# bombclock_1_0_1.net
KiCad netlist of a schematic drawn in EAGLE
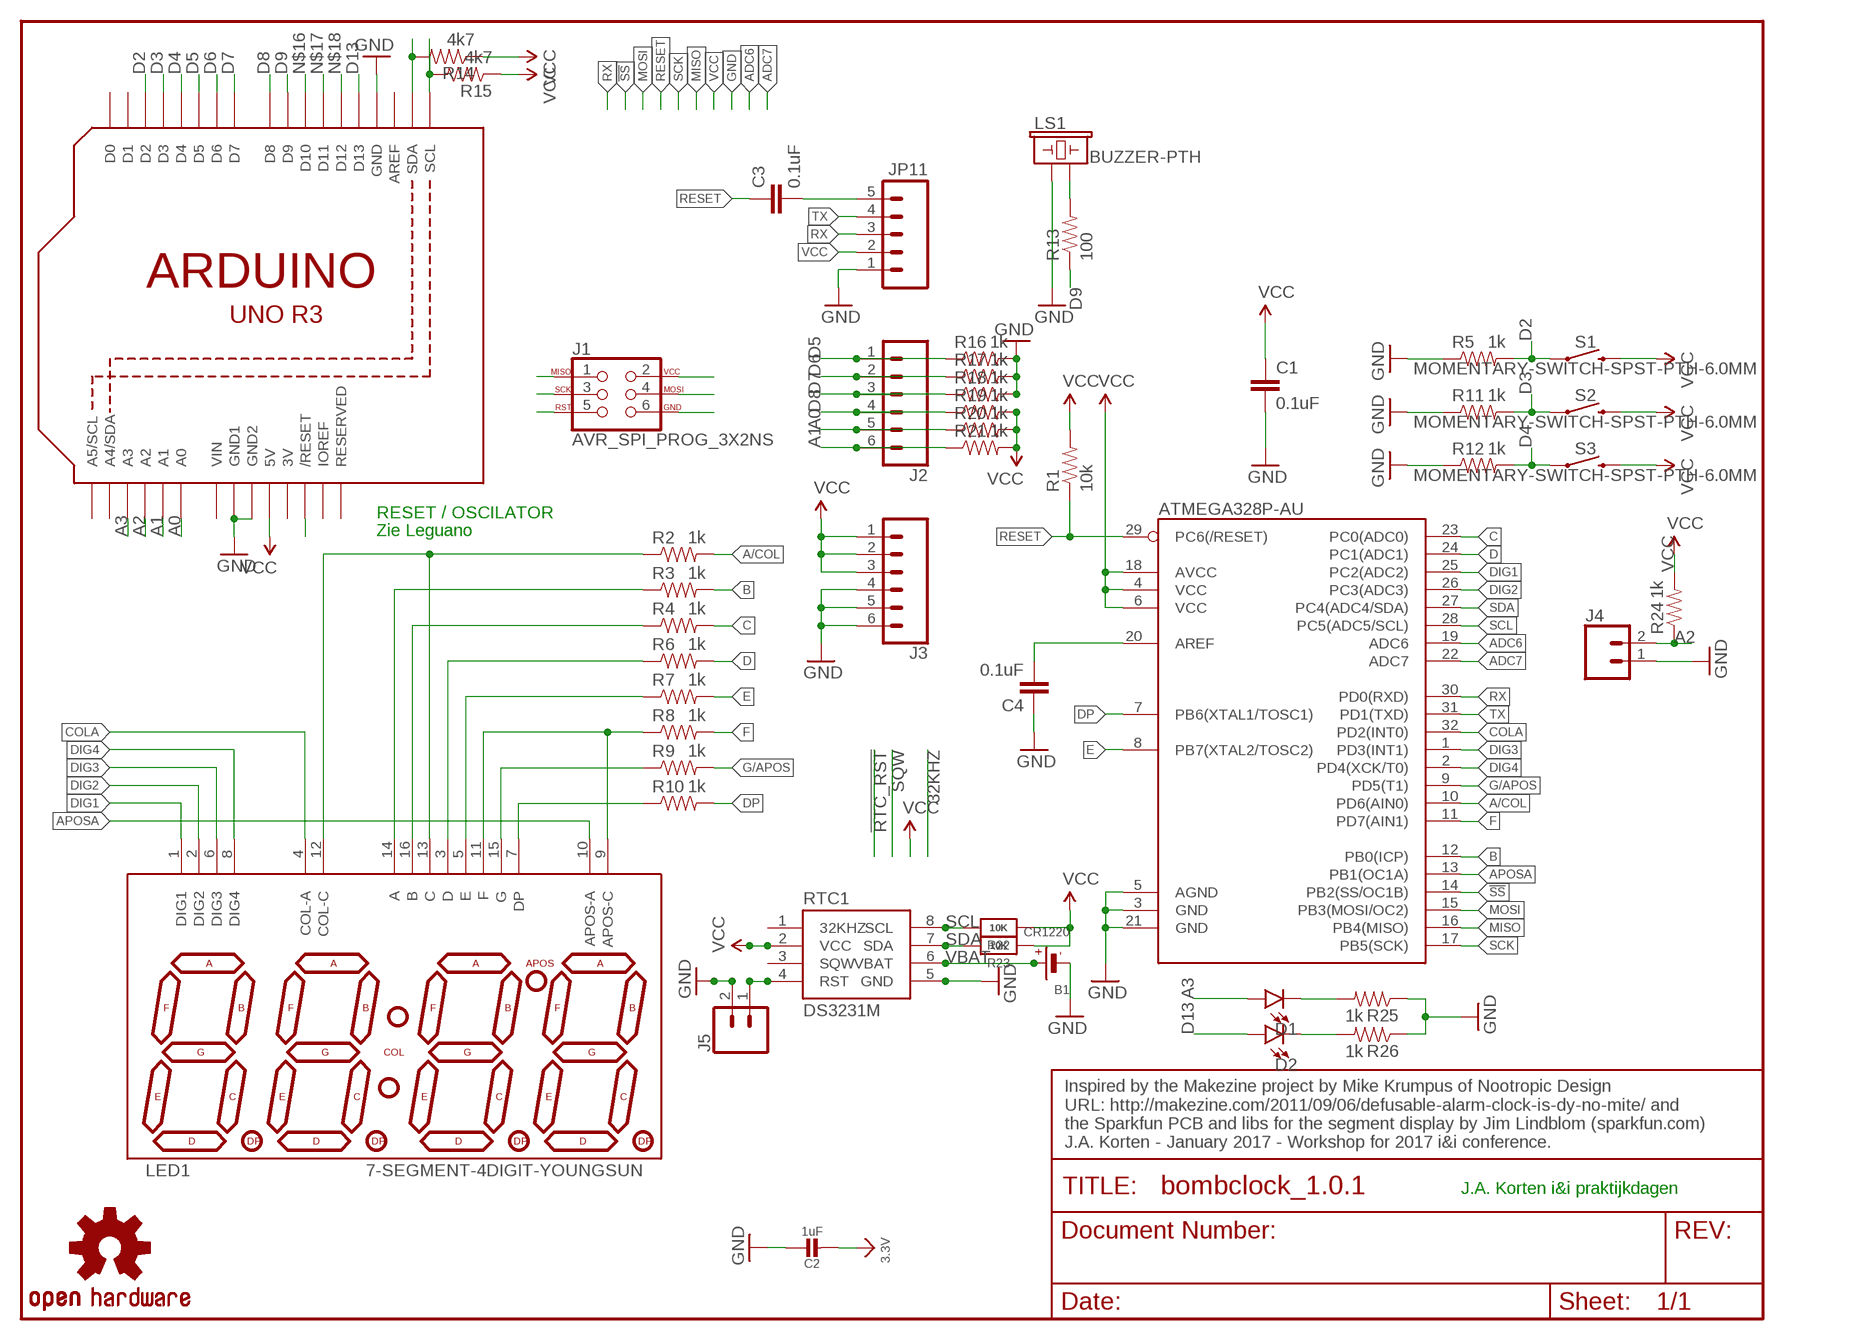
[diagram p0: schematic, sheet 1]

(export (version "E")
  (design (tool "Eeschema 10.0.6"))
  (components
    (comp (ref "ATMEGA328P-AU")
      (value "ATMEGA328P-AU")
      (footprint "eagle-import:TQFP32-08")
      (libsource (lib "eagle-import") (part "ATMEGA168"))
    )
    (comp (ref "B1")
      (value "CR1220")
      (footprint "eagle-import:CR1220")
      (libsource (lib "eagle-import") (part "BATTERYCR1220_SMT"))
    )
    (comp (ref "C1")
      (value "0.1uF")
      (footprint "eagle-import:0402-CAP")
      (libsource (lib "eagle-import") (part "CAP0402-CAP"))
    )
    (comp (ref "C2")
      (value "1uF")
      (footprint "eagle-import:0805-NO")
      (libsource (lib "eagle-import") (part "CAP_CERAMIC0805-NOOUTLINE"))
    )
    (comp (ref "C3")
      (value "0.1uF")
      (footprint "eagle-import:0402-CAP")
      (libsource (lib "eagle-import") (part "SparkFun-Passives_CAP0402-CAP"))
    )
    (comp (ref "C4")
      (value "0.1uF")
      (footprint "eagle-import:0402-CAP")
      (libsource (lib "eagle-import") (part "SparkFun-Passives_CAP0402-CAP"))
    )
    (comp (ref "D1")
      (value "LED5MM")
      (footprint "eagle-import:LED_5MM")
      (libsource (lib "eagle-import") (part "LED5MM"))
    )
    (comp (ref "D2")
      (value "LED5MM")
      (footprint "eagle-import:LED_5MM")
      (libsource (lib "eagle-import") (part "LED5MM"))
    )
    (comp (ref "J1")
      (value "AVR_SPI_PROG_3X2NS")
      (footprint "eagle-import:2X3-NS")
      (libsource (lib "eagle-import") (part "AVR_SPI_PROG_3X2NS"))
    )
    (comp (ref "J2")
      (value "CONN_06SILK_FEMALE_PTH")
      (footprint "eagle-import:1X06")
      (libsource (lib "eagle-import") (part "CONN_06SILK_FEMALE_PTH"))
    )
    (comp (ref "J3")
      (value "CONN_06SILK_FEMALE_PTH")
      (footprint "eagle-import:1X06")
      (libsource (lib "eagle-import") (part "CONN_06SILK_FEMALE_PTH"))
    )
    (comp (ref "J4")
      (value "CONN_02")
      (footprint "eagle-import:1X02")
      (libsource (lib "eagle-import") (part "CONN_02"))
    )
    (comp (ref "J5")
      (value "CONN_02")
      (footprint "eagle-import:1X02")
      (libsource (lib "eagle-import") (part "CONN_02"))
    )
    (comp (ref "JP11")
      (value "M05PTH-NS")
      (footprint "eagle-import:1X05_NO_SILK")
      (libsource (lib "eagle-import") (part "M05PTH-NS"))
    )
    (comp (ref "LED1")
      (value "7-SEGMENT-4DIGIT-YOUNGSUN")
      (footprint "eagle-import:7-SEGMENT-4DIGIT-YOUNGSUN")
      (libsource (lib "eagle-import") (part "7-SEGMENT-4DIGIT-YOUNGSUN"))
    )
    (comp (ref "LS1")
      (value "BUZZER-PTH")
      (footprint "eagle-import:BUZZER-12MM")
      (libsource (lib "eagle-import") (part "BUZZER-PTH"))
    )
    (comp (ref "R1")
      (value "10k")
      (footprint "eagle-import:0402-RES")
      (libsource (lib "eagle-import") (part "RESISTOR0402-RES"))
    )
    (comp (ref "R2")
      (value "1k")
      (footprint "eagle-import:0402-RES")
      (libsource (lib "eagle-import") (part "RESISTOR0402-RES"))
    )
    (comp (ref "R3")
      (value "1k")
      (footprint "eagle-import:0402-RES")
      (libsource (lib "eagle-import") (part "RESISTOR0402-RES"))
    )
    (comp (ref "R4")
      (value "1k")
      (footprint "eagle-import:0402-RES")
      (libsource (lib "eagle-import") (part "RESISTOR0402-RES"))
    )
    (comp (ref "R5")
      (value "1k")
      (footprint "eagle-import:0402-RES")
      (libsource (lib "eagle-import") (part "RESISTOR0402-RES"))
    )
    (comp (ref "R6")
      (value "1k")
      (footprint "eagle-import:0402-RES")
      (libsource (lib "eagle-import") (part "RESISTOR0402-RES"))
    )
    (comp (ref "R7")
      (value "1k")
      (footprint "eagle-import:0402-RES")
      (libsource (lib "eagle-import") (part "RESISTOR0402-RES"))
    )
    (comp (ref "R8")
      (value "1k")
      (footprint "eagle-import:0402-RES")
      (libsource (lib "eagle-import") (part "RESISTOR0402-RES"))
    )
    (comp (ref "R9")
      (value "1k")
      (footprint "eagle-import:0402-RES")
      (libsource (lib "eagle-import") (part "RESISTOR0402-RES"))
    )
    (comp (ref "R10")
      (value "1k")
      (footprint "eagle-import:0402-RES")
      (libsource (lib "eagle-import") (part "RESISTOR0402-RES"))
    )
    (comp (ref "R11")
      (value "1k")
      (footprint "eagle-import:0402-RES")
      (libsource (lib "eagle-import") (part "RESISTOR0402-RES"))
    )
    (comp (ref "R12")
      (value "1k")
      (footprint "eagle-import:0402-RES")
      (libsource (lib "eagle-import") (part "RESISTOR0402-RES"))
    )
    (comp (ref "R13")
      (value "100")
      (footprint "eagle-import:0402-RES")
      (libsource (lib "eagle-import") (part "RESISTOR0402-RES"))
    )
    (comp (ref "R14")
      (value "4k7")
      (footprint "eagle-import:0402-RES")
      (libsource (lib "eagle-import") (part "RESISTOR0402-RES"))
    )
    (comp (ref "R15")
      (value "4k7")
      (footprint "eagle-import:0402-RES")
      (libsource (lib "eagle-import") (part "RESISTOR0402-RES"))
    )
    (comp (ref "R16")
      (value "1k")
      (footprint "eagle-import:0402-RES")
      (libsource (lib "eagle-import") (part "RESISTOR0402-RES"))
    )
    (comp (ref "R17")
      (value "1k")
      (footprint "eagle-import:0402-RES")
      (libsource (lib "eagle-import") (part "RESISTOR0402-RES"))
    )
    (comp (ref "R18")
      (value "1k")
      (footprint "eagle-import:0402-RES")
      (libsource (lib "eagle-import") (part "RESISTOR0402-RES"))
    )
    (comp (ref "R19")
      (value "1k")
      (footprint "eagle-import:0402-RES")
      (libsource (lib "eagle-import") (part "RESISTOR0402-RES"))
    )
    (comp (ref "R20")
      (value "1k")
      (footprint "eagle-import:0402-RES")
      (libsource (lib "eagle-import") (part "RESISTOR0402-RES"))
    )
    (comp (ref "R21")
      (value "1k")
      (footprint "eagle-import:0402-RES")
      (libsource (lib "eagle-import") (part "RESISTOR0402-RES"))
    )
    (comp (ref "R22")
      (value "10K")
      (footprint "eagle-import:0805-NO")
      (libsource (lib "eagle-import") (part "RESISTOR0805_NOOUTLINE"))
    )
    (comp (ref "R23")
      (value "10K")
      (footprint "eagle-import:0805-NO")
      (libsource (lib "eagle-import") (part "RESISTOR0805_NOOUTLINE"))
    )
    (comp (ref "R24")
      (value "1k")
      (footprint "eagle-import:0402-RES")
      (libsource (lib "eagle-import") (part "RESISTOR0402-RES"))
    )
    (comp (ref "R25")
      (value "1k")
      (footprint "eagle-import:0402-RES")
      (libsource (lib "eagle-import") (part "RESISTOR0402-RES"))
    )
    (comp (ref "R26")
      (value "1k")
      (footprint "eagle-import:0402-RES")
      (libsource (lib "eagle-import") (part "RESISTOR0402-RES"))
    )
    (comp (ref "RTC1")
      (value "DS3231M")
      (footprint "eagle-import:SO08")
      (libsource (lib "eagle-import") (part "DS3231M"))
    )
    (comp (ref "S1")
      (value "MOMENTARY-SWITCH-SPST-PTH-6.0MM")
      (footprint "eagle-import:TACTILE_SWITCH_PTH_6.0MM")
      (libsource (lib "eagle-import") (part "MOMENTARY-SWITCH-SPST-PTH-6.0MM"))
    )
    (comp (ref "S2")
      (value "MOMENTARY-SWITCH-SPST-PTH-6.0MM")
      (footprint "eagle-import:TACTILE_SWITCH_PTH_6.0MM")
      (libsource (lib "eagle-import") (part "MOMENTARY-SWITCH-SPST-PTH-6.0MM"))
    )
    (comp (ref "S3")
      (value "MOMENTARY-SWITCH-SPST-PTH-6.0MM")
      (footprint "eagle-import:TACTILE_SWITCH_PTH_6.0MM")
      (libsource (lib "eagle-import") (part "MOMENTARY-SWITCH-SPST-PTH-6.0MM"))
    )
    (comp (ref "U$4")
      (value "OSHW-LOGOS")
      (footprint "eagle-import:OSHW-LOGO-S")
      (libsource (lib "eagle-import") (part "OSHW-LOGOS"))
    )
    (comp (ref "U1")
      (value "ARDUINOR3-DIMENSION")
      (footprint "eagle-import:ARDUINOR3")
      (libsource (lib "eagle-import") (part "ARDUINOR3-DIMENSION"))
    )
  )
  (nets
    (net (code "1") (name "/3V") (class "Default")
      (node (ref "U1") (pin "3V") (pinfunction "3V_3V") (pintype "power_in"))
    )
    (net (code "3") (name "/A0") (class "Default")
      (node (ref "J2") (pin "5") (pinfunction "5_5") (pintype "passive"))
      (node (ref "R20") (pin "1") (pinfunction "1_1") (pintype "passive"))
      (node (ref "U1") (pin "A0") (pinfunction "A0_A0") (pintype "bidirectional"))
    )
    (net (code "4") (name "/A1") (class "Default")
      (node (ref "J2") (pin "6") (pinfunction "6_6") (pintype "passive"))
      (node (ref "R21") (pin "1") (pinfunction "1_1") (pintype "passive"))
      (node (ref "U1") (pin "A1") (pinfunction "A1_A1") (pintype "bidirectional"))
    )
    (net (code "5") (name "/A2") (class "Default")
      (node (ref "J4") (pin "2") (pinfunction "2_2") (pintype "passive"))
      (node (ref "R24") (pin "1") (pinfunction "1_1") (pintype "passive"))
      (node (ref "U1") (pin "A2") (pinfunction "A2_A2") (pintype "bidirectional"))
    )
    (net (code "6") (name "/A3") (class "Default")
      (node (ref "D1") (pin "A") (pinfunction "A_A") (pintype "passive"))
      (node (ref "U1") (pin "A3") (pinfunction "A3_A3") (pintype "bidirectional"))
    )
    (net (code "7") (name "/D2") (class "Default")
      (node (ref "R5") (pin "2") (pinfunction "2_2") (pintype "passive"))
      (node (ref "S1") (pin "1") (pinfunction "1_1") (pintype "passive"))
      (node (ref "U1") (pin "D2") (pinfunction "D2_D2") (pintype "bidirectional"))
    )
    (net (code "8") (name "/D3") (class "Default")
      (node (ref "R11") (pin "2") (pinfunction "2_2") (pintype "passive"))
      (node (ref "S2") (pin "1") (pinfunction "1_1") (pintype "passive"))
      (node (ref "U1") (pin "D3") (pinfunction "D3_D3") (pintype "bidirectional"))
    )
    (net (code "9") (name "/D4") (class "Default")
      (node (ref "R12") (pin "2") (pinfunction "2_2") (pintype "passive"))
      (node (ref "S3") (pin "1") (pinfunction "1_1") (pintype "passive"))
      (node (ref "U1") (pin "D4") (pinfunction "D4_D4") (pintype "bidirectional"))
    )
    (net (code "10") (name "/D5") (class "Default")
      (node (ref "J2") (pin "1") (pinfunction "1_1") (pintype "passive"))
      (node (ref "R16") (pin "1") (pinfunction "1_1") (pintype "passive"))
      (node (ref "U1") (pin "D5") (pinfunction "D5_D5") (pintype "bidirectional"))
    )
    (net (code "11") (name "/D6") (class "Default")
      (node (ref "J2") (pin "2") (pinfunction "2_2") (pintype "passive"))
      (node (ref "R17") (pin "1") (pinfunction "1_1") (pintype "passive"))
      (node (ref "U1") (pin "D6") (pinfunction "D6_D6") (pintype "bidirectional"))
    )
    (net (code "12") (name "/D7") (class "Default")
      (node (ref "J2") (pin "3") (pinfunction "3_3") (pintype "passive"))
      (node (ref "R18") (pin "1") (pinfunction "1_1") (pintype "passive"))
      (node (ref "U1") (pin "D7") (pinfunction "D7_D7") (pintype "bidirectional"))
    )
    (net (code "13") (name "/D8") (class "Default")
      (node (ref "J2") (pin "4") (pinfunction "4_4") (pintype "passive"))
      (node (ref "R19") (pin "1") (pinfunction "1_1") (pintype "passive"))
      (node (ref "U1") (pin "D8") (pinfunction "D8_D8") (pintype "bidirectional"))
    )
    (net (code "14") (name "/D9") (class "Default")
      (node (ref "R13") (pin "1") (pinfunction "1_1") (pintype "passive"))
      (node (ref "U1") (pin "D9") (pinfunction "D9_D9") (pintype "bidirectional"))
    )
    (net (code "15") (name "/D13") (class "Default")
      (node (ref "D2") (pin "A") (pinfunction "A_A") (pintype "passive"))
      (node (ref "U1") (pin "D13") (pinfunction "D13_D13") (pintype "bidirectional"))
    )
    (net (code "16") (name "/N$16") (class "Default")
      (node (ref "U1") (pin "D10") (pinfunction "D10_D10") (pintype "bidirectional"))
    )
    (net (code "17") (name "/N$17") (class "Default")
      (node (ref "U1") (pin "D11") (pinfunction "D11_D11") (pintype "bidirectional"))
    )
    (net (code "18") (name "/N$18") (class "Default")
      (node (ref "U1") (pin "D12") (pinfunction "D12_D12") (pintype "bidirectional"))
    )
    (net (code "20") (name "/VBAT") (class "Default")
      (node (ref "B1") (pin "+$1") (pinfunction "+_+$1") (pintype "passive"))
      (node (ref "RTC1") (pin "6") (pinfunction "VBAT_6") (pintype "power_in"))
    )
    (net (code "21") (name "/VIN") (class "Default")
      (node (ref "U1") (pin "VIN") (pinfunction "VIN_VIN") (pintype "power_in"))
    )
    (net (code "23") (name "/~{SS}") (class "Default")
      (node (ref "ATMEGA328P-AU") (pin "14") (pinfunction "PB2(SS/OC1B)_14") (pintype "bidirectional"))
    )
    (net (code "24") (name "3.3V") (class "Default")
      (node (ref "C2") (pin "2") (pinfunction "2_2") (pintype "passive"))
    )
    (net (code "25") (name "ADC6") (class "Default")
      (node (ref "ATMEGA328P-AU") (pin "19") (pinfunction "ADC6_19") (pintype "bidirectional"))
    )
    (net (code "26") (name "ADC7") (class "Default")
      (node (ref "ATMEGA328P-AU") (pin "22") (pinfunction "ADC7_22") (pintype "bidirectional"))
    )
    (net (code "27") (name "APOSA") (class "Default")
      (node (ref "ATMEGA328P-AU") (pin "13") (pinfunction "PB1(OC1A)_13") (pintype "bidirectional"))
      (node (ref "LED1") (pin "10") (pinfunction "APOS-A_10") (pintype "bidirectional"))
    )
    (net (code "28") (name "A{slash}COL") (class "Default")
      (node (ref "ATMEGA328P-AU") (pin "10") (pinfunction "PD6(AIN0)_10") (pintype "bidirectional"))
      (node (ref "R2") (pin "2") (pinfunction "2_2") (pintype "passive"))
    )
    (net (code "29") (name "B") (class "Default")
      (node (ref "ATMEGA328P-AU") (pin "12") (pinfunction "PB0(ICP)_12") (pintype "bidirectional"))
      (node (ref "R3") (pin "2") (pinfunction "2_2") (pintype "passive"))
    )
    (net (code "30") (name "C") (class "Default")
      (node (ref "ATMEGA328P-AU") (pin "23") (pinfunction "PC0(ADC0)_23") (pintype "bidirectional"))
      (node (ref "R4") (pin "2") (pinfunction "2_2") (pintype "passive"))
    )
    (net (code "31") (name "COLA") (class "Default")
      (node (ref "ATMEGA328P-AU") (pin "32") (pinfunction "PD2(INT0)_32") (pintype "bidirectional"))
      (node (ref "LED1") (pin "4") (pinfunction "COL-A_4") (pintype "bidirectional"))
    )
    (net (code "32") (name "D") (class "Default")
      (node (ref "ATMEGA328P-AU") (pin "24") (pinfunction "PC1(ADC1)_24") (pintype "bidirectional"))
      (node (ref "R6") (pin "2") (pinfunction "2_2") (pintype "passive"))
    )
    (net (code "33") (name "DIG1") (class "Default")
      (node (ref "ATMEGA328P-AU") (pin "25") (pinfunction "PC2(ADC2)_25") (pintype "bidirectional"))
      (node (ref "LED1") (pin "1") (pinfunction "DIG1_1") (pintype "bidirectional"))
    )
    (net (code "34") (name "DIG2") (class "Default")
      (node (ref "ATMEGA328P-AU") (pin "26") (pinfunction "PC3(ADC3)_26") (pintype "bidirectional"))
      (node (ref "LED1") (pin "2") (pinfunction "DIG2_2") (pintype "bidirectional"))
    )
    (net (code "35") (name "DIG3") (class "Default")
      (node (ref "ATMEGA328P-AU") (pin "1") (pinfunction "PD3(INT1)_1") (pintype "bidirectional"))
      (node (ref "LED1") (pin "6") (pinfunction "DIG3_6") (pintype "bidirectional"))
    )
    (net (code "36") (name "DIG4") (class "Default")
      (node (ref "ATMEGA328P-AU") (pin "2") (pinfunction "PD4(XCK/T0)_2") (pintype "bidirectional"))
      (node (ref "LED1") (pin "8") (pinfunction "DIG4_8") (pintype "bidirectional"))
    )
    (net (code "37") (name "DP") (class "Default")
      (node (ref "ATMEGA328P-AU") (pin "7") (pinfunction "PB6(XTAL1/TOSC1)_7") (pintype "bidirectional"))
      (node (ref "R10") (pin "2") (pinfunction "2_2") (pintype "passive"))
    )
    (net (code "38") (name "E") (class "Default")
      (node (ref "ATMEGA328P-AU") (pin "8") (pinfunction "PB7(XTAL2/TOSC2)_8") (pintype "bidirectional"))
      (node (ref "R7") (pin "2") (pinfunction "2_2") (pintype "passive"))
    )
    (net (code "39") (name "F") (class "Default")
      (node (ref "ATMEGA328P-AU") (pin "11") (pinfunction "PD7(AIN1)_11") (pintype "bidirectional"))
      (node (ref "R8") (pin "2") (pinfunction "2_2") (pintype "passive"))
    )
    (net (code "40") (name "GND") (class "Default")
      (node (ref "ATMEGA328P-AU") (pin "21") (pinfunction "GND_21") (pintype "bidirectional"))
      (node (ref "ATMEGA328P-AU") (pin "3") (pinfunction "GND_3") (pintype "bidirectional"))
      (node (ref "ATMEGA328P-AU") (pin "5") (pinfunction "AGND_5") (pintype "bidirectional"))
      (node (ref "B1") (pin "-") (pinfunction "-_-") (pintype "passive"))
      (node (ref "C1") (pin "2") (pinfunction "2_2") (pintype "passive"))
      (node (ref "C2") (pin "1") (pinfunction "1_1") (pintype "passive"))
      (node (ref "C4") (pin "1") (pinfunction "1_1") (pintype "passive"))
      (node (ref "J1") (pin "6") (pinfunction "6_6") (pintype "passive"))
      (node (ref "J3") (pin "4") (pinfunction "4_4") (pintype "passive"))
      (node (ref "J3") (pin "5") (pinfunction "5_5") (pintype "passive"))
      (node (ref "J3") (pin "6") (pinfunction "6_6") (pintype "passive"))
      (node (ref "J4") (pin "1") (pinfunction "1_1") (pintype "passive"))
      (node (ref "J5") (pin "2") (pinfunction "2_2") (pintype "passive"))
      (node (ref "JP11") (pin "1") (pinfunction "1_1") (pintype "passive"))
      (node (ref "LS1") (pin "+") (pinfunction "1_+") (pintype "passive"))
      (node (ref "R11") (pin "1") (pinfunction "1_1") (pintype "passive"))
      (node (ref "R12") (pin "1") (pinfunction "1_1") (pintype "passive"))
      (node (ref "R16") (pin "2") (pinfunction "2_2") (pintype "passive"))
      (node (ref "R17") (pin "2") (pinfunction "2_2") (pintype "passive"))
      (node (ref "R18") (pin "2") (pinfunction "2_2") (pintype "passive"))
      (node (ref "R25") (pin "1") (pinfunction "1_1") (pintype "passive"))
      (node (ref "R26") (pin "1") (pinfunction "1_1") (pintype "passive"))
      (node (ref "R5") (pin "1") (pinfunction "1_1") (pintype "passive"))
      (node (ref "RTC1") (pin "5") (pinfunction "GND_5") (pintype "power_in"))
      (node (ref "U1") (pin "GND") (pinfunction "GND_GND") (pintype "power_in"))
      (node (ref "U1") (pin "GND1") (pinfunction "GND1_GND1") (pintype "power_in"))
      (node (ref "U1") (pin "GND2") (pinfunction "GND2_GND2") (pintype "power_in"))
    )
    (net (code "41") (name "G{slash}APOS") (class "Default")
      (node (ref "ATMEGA328P-AU") (pin "9") (pinfunction "PD5(T1)_9") (pintype "bidirectional"))
      (node (ref "R9") (pin "2") (pinfunction "2_2") (pintype "passive"))
    )
    (net (code "42") (name "MISO") (class "Default")
      (node (ref "ATMEGA328P-AU") (pin "16") (pinfunction "PB4(MISO)_16") (pintype "bidirectional"))
      (node (ref "J1") (pin "1") (pinfunction "1_1") (pintype "passive"))
    )
    (net (code "43") (name "MOSI") (class "Default")
      (node (ref "ATMEGA328P-AU") (pin "15") (pinfunction "PB3(MOSI/OC2)_15") (pintype "bidirectional"))
      (node (ref "J1") (pin "4") (pinfunction "4_4") (pintype "passive"))
    )
    (net (code "44") (name "Net-(ATMEGA328P-AU-AREF)") (class "Default")
      (node (ref "ATMEGA328P-AU") (pin "20") (pinfunction "AREF_20") (pintype "bidirectional"))
      (node (ref "C4") (pin "2") (pinfunction "2_2") (pintype "passive"))
    )
    (net (code "45") (name "Net-(C3-Pad2)") (class "Default")
      (node (ref "C3") (pin "2") (pinfunction "2_2") (pintype "passive"))
      (node (ref "JP11") (pin "5") (pinfunction "5_5") (pintype "passive"))
    )
    (net (code "46") (name "Net-(D1-C)") (class "Default")
      (node (ref "D1") (pin "K") (pinfunction "C_K") (pintype "passive"))
      (node (ref "R25") (pin "2") (pinfunction "2_2") (pintype "passive"))
    )
    (net (code "47") (name "Net-(D2-C)") (class "Default")
      (node (ref "D2") (pin "K") (pinfunction "C_K") (pintype "passive"))
      (node (ref "R26") (pin "2") (pinfunction "2_2") (pintype "passive"))
    )
    (net (code "48") (name "Net-(LED1-A)") (class "Default")
      (node (ref "LED1") (pin "14") (pinfunction "A_14") (pintype "bidirectional"))
      (node (ref "R3") (pin "1") (pinfunction "1_1") (pintype "passive"))
    )
    (net (code "49") (name "Net-(LED1-APOS-C)") (class "Default")
      (node (ref "LED1") (pin "11") (pinfunction "F_11") (pintype "bidirectional"))
      (node (ref "LED1") (pin "9") (pinfunction "APOS-C_9") (pintype "bidirectional"))
      (node (ref "R8") (pin "1") (pinfunction "1_1") (pintype "passive"))
    )
    (net (code "50") (name "Net-(LED1-B)") (class "Default")
      (node (ref "LED1") (pin "16") (pinfunction "B_16") (pintype "bidirectional"))
      (node (ref "R4") (pin "1") (pinfunction "1_1") (pintype "passive"))
    )
    (net (code "51") (name "Net-(LED1-C)") (class "Default")
      (node (ref "LED1") (pin "12") (pinfunction "COL-C_12") (pintype "bidirectional"))
      (node (ref "LED1") (pin "13") (pinfunction "C_13") (pintype "bidirectional"))
      (node (ref "R2") (pin "1") (pinfunction "1_1") (pintype "passive"))
    )
    (net (code "52") (name "Net-(LED1-D)") (class "Default")
      (node (ref "LED1") (pin "3") (pinfunction "D_3") (pintype "bidirectional"))
      (node (ref "R6") (pin "1") (pinfunction "1_1") (pintype "passive"))
    )
    (net (code "53") (name "Net-(LED1-DP)") (class "Default")
      (node (ref "LED1") (pin "7") (pinfunction "DP_7") (pintype "bidirectional"))
      (node (ref "R10") (pin "1") (pinfunction "1_1") (pintype "passive"))
    )
    (net (code "54") (name "Net-(LED1-E)") (class "Default")
      (node (ref "LED1") (pin "5") (pinfunction "E_5") (pintype "bidirectional"))
      (node (ref "R7") (pin "1") (pinfunction "1_1") (pintype "passive"))
    )
    (net (code "55") (name "Net-(LED1-G)") (class "Default")
      (node (ref "LED1") (pin "15") (pinfunction "G_15") (pintype "bidirectional"))
      (node (ref "R9") (pin "1") (pinfunction "1_1") (pintype "passive"))
    )
    (net (code "56") (name "Net-(LS1-2)") (class "Default")
      (node (ref "LS1") (pin "-") (pinfunction "2_-") (pintype "passive"))
      (node (ref "R13") (pin "2") (pinfunction "2_2") (pintype "passive"))
    )
    (net (code "57") (name "Net-(RTC1-RST)") (class "Default")
      (node (ref "J5") (pin "1") (pinfunction "1_1") (pintype "passive"))
      (node (ref "RTC1") (pin "4") (pinfunction "RST_4") (pintype "bidirectional"))
    )
    (net (code "58") (name "RESET") (class "Default")
      (node (ref "ATMEGA328P-AU") (pin "29") (pinfunction "PC6(/RESET)_29") (pintype "bidirectional"))
      (node (ref "C3") (pin "1") (pinfunction "1_1") (pintype "passive"))
      (node (ref "J1") (pin "5") (pinfunction "5_5") (pintype "passive"))
      (node (ref "R1") (pin "1") (pinfunction "1_1") (pintype "passive"))
    )
    (net (code "59") (name "RX") (class "Default")
      (node (ref "ATMEGA328P-AU") (pin "30") (pinfunction "PD0(RXD)_30") (pintype "bidirectional"))
      (node (ref "JP11") (pin "3") (pinfunction "3_3") (pintype "passive"))
    )
    (net (code "60") (name "SCK") (class "Default")
      (node (ref "ATMEGA328P-AU") (pin "17") (pinfunction "PB5(SCK)_17") (pintype "bidirectional"))
      (node (ref "J1") (pin "3") (pinfunction "3_3") (pintype "passive"))
    )
    (net (code "61") (name "SCL") (class "Default")
      (node (ref "ATMEGA328P-AU") (pin "28") (pinfunction "PC5(ADC5/SCL)_28") (pintype "bidirectional"))
      (node (ref "R15") (pin "2") (pinfunction "2_2") (pintype "passive"))
      (node (ref "R22") (pin "2") (pinfunction "2_2") (pintype "passive"))
      (node (ref "RTC1") (pin "8") (pinfunction "SCL_8") (pintype "bidirectional"))
      (node (ref "U1") (pin "SCL") (pinfunction "SCL_SCL") (pintype "bidirectional"))
    )
    (net (code "62") (name "SDA") (class "Default")
      (node (ref "ATMEGA328P-AU") (pin "27") (pinfunction "PC4(ADC4/SDA)_27") (pintype "bidirectional"))
      (node (ref "R14") (pin "2") (pinfunction "2_2") (pintype "passive"))
      (node (ref "R23") (pin "2") (pinfunction "2_2") (pintype "passive"))
      (node (ref "RTC1") (pin "7") (pinfunction "SDA_7") (pintype "bidirectional"))
      (node (ref "U1") (pin "SDA") (pinfunction "SDA_SDA") (pintype "bidirectional"))
    )
    (net (code "63") (name "TX") (class "Default")
      (node (ref "ATMEGA328P-AU") (pin "31") (pinfunction "PD1(TXD)_31") (pintype "bidirectional"))
      (node (ref "JP11") (pin "4") (pinfunction "4_4") (pintype "passive"))
    )
    (net (code "64") (name "VCC") (class "Default")
      (node (ref "ATMEGA328P-AU") (pin "18") (pinfunction "AVCC_18") (pintype "bidirectional"))
      (node (ref "ATMEGA328P-AU") (pin "4") (pinfunction "VCC_4") (pintype "bidirectional"))
      (node (ref "ATMEGA328P-AU") (pin "6") (pinfunction "VCC_6") (pintype "bidirectional"))
      (node (ref "C1") (pin "1") (pinfunction "1_1") (pintype "passive"))
      (node (ref "J1") (pin "2") (pinfunction "2_2") (pintype "passive"))
      (node (ref "J3") (pin "1") (pinfunction "1_1") (pintype "passive"))
      (node (ref "J3") (pin "2") (pinfunction "2_2") (pintype "passive"))
      (node (ref "J3") (pin "3") (pinfunction "3_3") (pintype "passive"))
      (node (ref "JP11") (pin "2") (pinfunction "2_2") (pintype "passive"))
      (node (ref "R1") (pin "2") (pinfunction "2_2") (pintype "passive"))
      (node (ref "R14") (pin "1") (pinfunction "1_1") (pintype "passive"))
      (node (ref "R15") (pin "1") (pinfunction "1_1") (pintype "passive"))
      (node (ref "R19") (pin "2") (pinfunction "2_2") (pintype "passive"))
      (node (ref "R20") (pin "2") (pinfunction "2_2") (pintype "passive"))
      (node (ref "R21") (pin "2") (pinfunction "2_2") (pintype "passive"))
      (node (ref "R22") (pin "1") (pinfunction "1_1") (pintype "passive"))
      (node (ref "R23") (pin "1") (pinfunction "1_1") (pintype "passive"))
      (node (ref "R24") (pin "2") (pinfunction "2_2") (pintype "passive"))
      (node (ref "RTC1") (pin "2") (pinfunction "VCC_2") (pintype "power_in"))
      (node (ref "S1") (pin "3") (pinfunction "2_3") (pintype "passive"))
      (node (ref "S2") (pin "3") (pinfunction "2_3") (pintype "passive"))
      (node (ref "S3") (pin "3") (pinfunction "2_3") (pintype "passive"))
      (node (ref "U1") (pin "5V") (pinfunction "5V_5V") (pintype "power_in"))
    )
    (net (code "65") (name "unconnected-(RTC1-32KHZ-Pad1)") (class "Default")
      (node (ref "RTC1") (pin "1") (pinfunction "32KHZ_1") (pintype "output"))
    )
    (net (code "66") (name "unconnected-(RTC1-SQW-Pad3)") (class "Default")
      (node (ref "RTC1") (pin "3") (pinfunction "SQW_3") (pintype "output"))
    )
    (net (code "67") (name "unconnected-(U1-A4{slash}SDA-PadA4)") (class "Default")
      (node (ref "U1") (pin "A4") (pinfunction "A4/SDA_A4") (pintype "bidirectional"))
    )
    (net (code "68") (name "unconnected-(U1-A5{slash}SCL-PadA5)") (class "Default")
      (node (ref "U1") (pin "A5") (pinfunction "A5/SCL_A5") (pintype "bidirectional"))
    )
    (net (code "69") (name "unconnected-(U1-PadAREF)") (class "Default")
      (node (ref "U1") (pin "AREF") (pinfunction "AREF_AREF") (pintype "bidirectional"))
    )
    (net (code "70") (name "unconnected-(U1-PadD0)") (class "Default")
      (node (ref "U1") (pin "D0") (pinfunction "D0_D0") (pintype "bidirectional"))
    )
    (net (code "71") (name "unconnected-(U1-PadD1)") (class "Default")
      (node (ref "U1") (pin "D1") (pinfunction "D1_D1") (pintype "bidirectional"))
    )
    (net (code "72") (name "unconnected-(U1-PadIOREF)") (class "Default")
      (node (ref "U1") (pin "IOREF") (pinfunction "IOREF_IOREF") (pintype "output"))
    )
    (net (code "73") (name "unconnected-(U1-PadRESERVED)") (class "Default")
      (node (ref "U1") (pin "RESERVED") (pinfunction "RESERVED_RESERVED") (pintype "no_connect"))
    )
    (net (code "74") (name "unconnected-(U1-{slash}RESET-PadRESET)") (class "Default")
      (node (ref "U1") (pin "RESET") (pinfunction "/RESET_RESET") (pintype "bidirectional"))
    )
  )
)
